# Placa.net
KiCad netlist of a schematic drawn in EAGLE
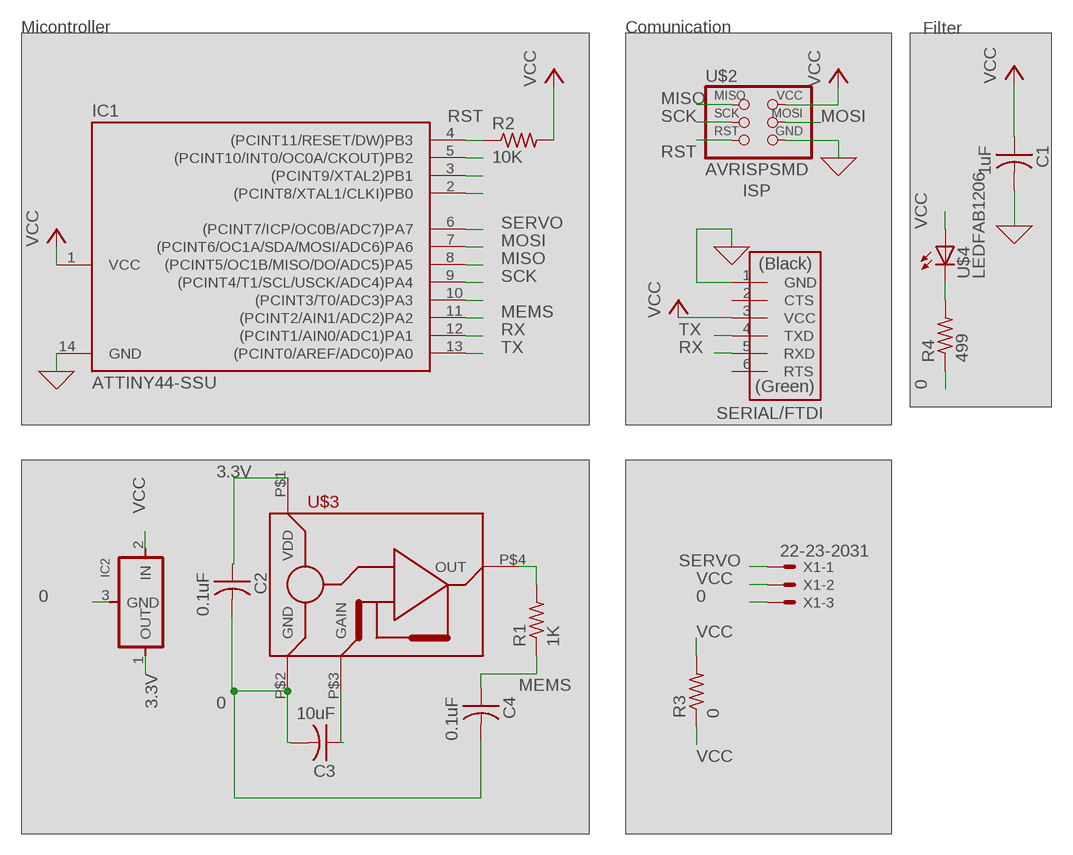
[diagram p0: schematic, sheet 1]

(export (version "E")
  (design (tool "Eeschema 10.0.6"))
  (components
    (comp (ref "C1")
      (value "1uF")
      (footprint "eagle-import:C1206FAB")
      (libsource (lib "eagle-import") (part "CAP-US1206FAB"))
    )
    (comp (ref "C2")
      (value "0.1uF")
      (footprint "eagle-import:C1206FAB")
      (libsource (lib "eagle-import") (part "CAP-US1206FAB"))
    )
    (comp (ref "C3")
      (value "10uF")
      (footprint "eagle-import:C1206FAB")
      (libsource (lib "eagle-import") (part "CAP-US1206FAB"))
    )
    (comp (ref "C4")
      (value "0.1uF")
      (footprint "eagle-import:C1206FAB")
      (libsource (lib "eagle-import") (part "CAP-US1206FAB"))
    )
    (comp (ref "IC1")
      (value "ATTINY44-SSU")
      (footprint "eagle-import:SOIC14")
      (libsource (lib "eagle-import") (part "ATTINY44-SSU"))
    )
    (comp (ref "IC2")
      (value "REGULATORSOT23")
      (footprint "eagle-import:SOT23")
      (libsource (lib "eagle-import") (part "REGULATORSOT23"))
    )
    (comp (ref "R1")
      (value "1K")
      (footprint "eagle-import:R1206FAB")
      (libsource (lib "eagle-import") (part "RES-US1206FAB"))
    )
    (comp (ref "R2")
      (value "10K")
      (footprint "eagle-import:R1206FAB")
      (libsource (lib "eagle-import") (part "RES-US1206FAB"))
    )
    (comp (ref "R3")
      (value "0")
      (footprint "eagle-import:R1206FAB")
      (libsource (lib "eagle-import") (part "RES-US1206FAB"))
    )
    (comp (ref "R4")
      (value "499")
      (footprint "eagle-import:R1206FAB")
      (libsource (lib "eagle-import") (part "RES-US1206FAB"))
    )
    (comp (ref "U$1")
      (value "FTDI-SMD-HEADER")
      (footprint "eagle-import:1X06SMD")
      (libsource (lib "eagle-import") (part "FTDI-SMD-HEADER"))
    )
    (comp (ref "U$2")
      (value "AVRISPSMD")
      (footprint "eagle-import:2X03SMD")
      (libsource (lib "eagle-import") (part "AVRISPSMD"))
    )
    (comp (ref "U$3")
      (value "MEMS_MIC_SPU0414HR5H-SB")
      (footprint "eagle-import:CSP-4PIN")
      (libsource (lib "eagle-import") (part "MEMS_MIC_SPU0414HR5H-SB"))
    )
    (comp (ref "U$4")
      (value "LEDFAB1206")
      (footprint "eagle-import:LED1206FAB")
      (libsource (lib "eagle-import") (part "LEDFAB1206"))
    )
    (comp (ref "X1")
      (value "22-23-2031")
      (footprint "eagle-import:22-23-2031")
      (fields (field (name "MF") "MOLEX"))
      (libsource (lib "eagle-import") (part "22-23-2031"))
    )
  )
  (nets
    (net (code "1") (name "/3.3V") (class "Default")
      (node (ref "C2") (pin "1") (pinfunction "1_1") (pintype "passive"))
      (node (ref "IC2") (pin "1") (pinfunction "OUT_1") (pintype "bidirectional"))
      (node (ref "U$3") (pin "P$1") (pinfunction "VDD_P$1") (pintype "bidirectional"))
    )
    (net (code "2") (name "/MEMS") (class "Default")
      (node (ref "C4") (pin "1") (pinfunction "1_1") (pintype "passive"))
      (node (ref "IC1") (pin "11") (pinfunction "(PCINT2/AIN1/ADC2)PA2_11") (pintype "bidirectional"))
      (node (ref "R1") (pin "1") (pinfunction "1_1") (pintype "passive"))
    )
    (net (code "3") (name "/MISO") (class "Default")
      (node (ref "IC1") (pin "8") (pinfunction "(PCINT5/OC1B/MISO/DO/ADC5)PA5_8") (pintype "bidirectional"))
      (node (ref "U$2") (pin "1") (pinfunction "MISO_1") (pintype "passive"))
    )
    (net (code "4") (name "/MOSI") (class "Default")
      (node (ref "IC1") (pin "7") (pinfunction "(PCINT6/OC1A/SDA/MOSI/ADC6)PA6_7") (pintype "bidirectional"))
      (node (ref "U$2") (pin "4") (pinfunction "MOSI_4") (pintype "passive"))
    )
    (net (code "5") (name "/RST") (class "Default")
      (node (ref "IC1") (pin "4") (pinfunction "(PCINT11/RESET/DW)PB3_4") (pintype "bidirectional"))
      (node (ref "R2") (pin "1") (pinfunction "1_1") (pintype "passive"))
      (node (ref "U$2") (pin "5") (pinfunction "RST_5") (pintype "passive"))
    )
    (net (code "6") (name "/RX") (class "Default")
      (node (ref "IC1") (pin "12") (pinfunction "(PCINT1/AIN0/ADC1)PA1_12") (pintype "bidirectional"))
      (node (ref "U$1") (pin "5") (pinfunction "RXD_5") (pintype "bidirectional"))
    )
    (net (code "7") (name "/SCK") (class "Default")
      (node (ref "IC1") (pin "9") (pinfunction "(PCINT4/T1/SCL/USCK/ADC4)PA4_9") (pintype "bidirectional"))
      (node (ref "U$2") (pin "3") (pinfunction "SCK_3") (pintype "passive"))
    )
    (net (code "8") (name "/SERVO") (class "Default")
      (node (ref "IC1") (pin "6") (pinfunction "(PCINT7/ICP/OC0B/ADC7)PA7_6") (pintype "bidirectional"))
      (node (ref "X1") (pin "1") (pinfunction "S_1") (pintype "passive"))
    )
    (net (code "9") (name "/TX") (class "Default")
      (node (ref "IC1") (pin "13") (pinfunction "(PCINT0/AREF/ADC0)PA0_13") (pintype "bidirectional"))
      (node (ref "U$1") (pin "4") (pinfunction "TXD_4") (pintype "bidirectional"))
    )
    (net (code "10") (name "GND") (class "Default")
      (node (ref "C1") (pin "2") (pinfunction "2_2") (pintype "passive"))
      (node (ref "C2") (pin "2") (pinfunction "2_2") (pintype "passive"))
      (node (ref "C3") (pin "2") (pinfunction "2_2") (pintype "passive"))
      (node (ref "C4") (pin "2") (pinfunction "2_2") (pintype "passive"))
      (node (ref "IC1") (pin "14") (pinfunction "GND_14") (pintype "power_in"))
      (node (ref "IC2") (pin "3") (pinfunction "GND_3") (pintype "bidirectional"))
      (node (ref "R4") (pin "1") (pinfunction "1_1") (pintype "passive"))
      (node (ref "U$1") (pin "1") (pinfunction "GND_1") (pintype "bidirectional"))
      (node (ref "U$2") (pin "6") (pinfunction "GND_6") (pintype "passive"))
      (node (ref "U$3") (pin "P$2") (pinfunction "GND_P$2") (pintype "bidirectional"))
      (node (ref "X1") (pin "3") (pinfunction "S_3") (pintype "passive"))
    )
    (net (code "11") (name "Net-(U$3-GAIN)") (class "Default")
      (node (ref "C3") (pin "1") (pinfunction "1_1") (pintype "passive"))
      (node (ref "U$3") (pin "P$3") (pinfunction "GAIN_P$3") (pintype "bidirectional"))
    )
    (net (code "12") (name "Net-(U$3-OUT)") (class "Default")
      (node (ref "R1") (pin "2") (pinfunction "2_2") (pintype "passive"))
      (node (ref "U$3") (pin "P$4") (pinfunction "OUT_P$4") (pintype "bidirectional"))
    )
    (net (code "13") (name "Net-(U$4-C)") (class "Default")
      (node (ref "R4") (pin "2") (pinfunction "2_2") (pintype "passive"))
      (node (ref "U$4") (pin "2") (pinfunction "C_2") (pintype "passive"))
    )
    (net (code "14") (name "VCC") (class "Default")
      (node (ref "C1") (pin "1") (pinfunction "1_1") (pintype "passive"))
      (node (ref "IC1") (pin "1") (pinfunction "VCC_1") (pintype "power_in"))
      (node (ref "IC2") (pin "2") (pinfunction "IN_2") (pintype "bidirectional"))
      (node (ref "R2") (pin "2") (pinfunction "2_2") (pintype "passive"))
      (node (ref "R3") (pin "1") (pinfunction "1_1") (pintype "passive"))
      (node (ref "R3") (pin "2") (pinfunction "2_2") (pintype "passive"))
      (node (ref "U$1") (pin "3") (pinfunction "VCC_3") (pintype "bidirectional"))
      (node (ref "U$2") (pin "2") (pinfunction "VCC_2") (pintype "passive"))
      (node (ref "U$4") (pin "1") (pinfunction "A_1") (pintype "passive"))
      (node (ref "X1") (pin "2") (pinfunction "S_2") (pintype "passive"))
    )
    (net (code "15") (name "unconnected-(IC1-(PCINT3{slash}T0{slash}ADC3)PA3-Pad10)") (class "Default")
      (node (ref "IC1") (pin "10") (pinfunction "(PCINT3/T0/ADC3)PA3_10") (pintype "bidirectional"))
    )
    (net (code "16") (name "unconnected-(IC1-(PCINT8{slash}XTAL1{slash}CLKI)PB0-Pad2)") (class "Default")
      (node (ref "IC1") (pin "2") (pinfunction "(PCINT8/XTAL1/CLKI)PB0_2") (pintype "bidirectional"))
    )
    (net (code "17") (name "unconnected-(IC1-(PCINT9{slash}XTAL2)PB1-Pad3)") (class "Default")
      (node (ref "IC1") (pin "3") (pinfunction "(PCINT9/XTAL2)PB1_3") (pintype "bidirectional"))
    )
    (net (code "18") (name "unconnected-(IC1-(PCINT10{slash}INT0{slash}OC0A{slash}CKOUT)PB2-Pad5)") (class "Default")
      (node (ref "IC1") (pin "5") (pinfunction "(PCINT10/INT0/OC0A/CKOUT)PB2_5") (pintype "bidirectional"))
    )
    (net (code "19") (name "unconnected-(U$1-CTS-Pad2)") (class "Default")
      (node (ref "U$1") (pin "2") (pinfunction "CTS_2") (pintype "bidirectional"))
    )
    (net (code "20") (name "unconnected-(U$1-RTS-Pad6)") (class "Default")
      (node (ref "U$1") (pin "6") (pinfunction "RTS_6") (pintype "bidirectional"))
    )
  )
)
